# ECG.net
KiCad netlist of a schematic drawn in EAGLE
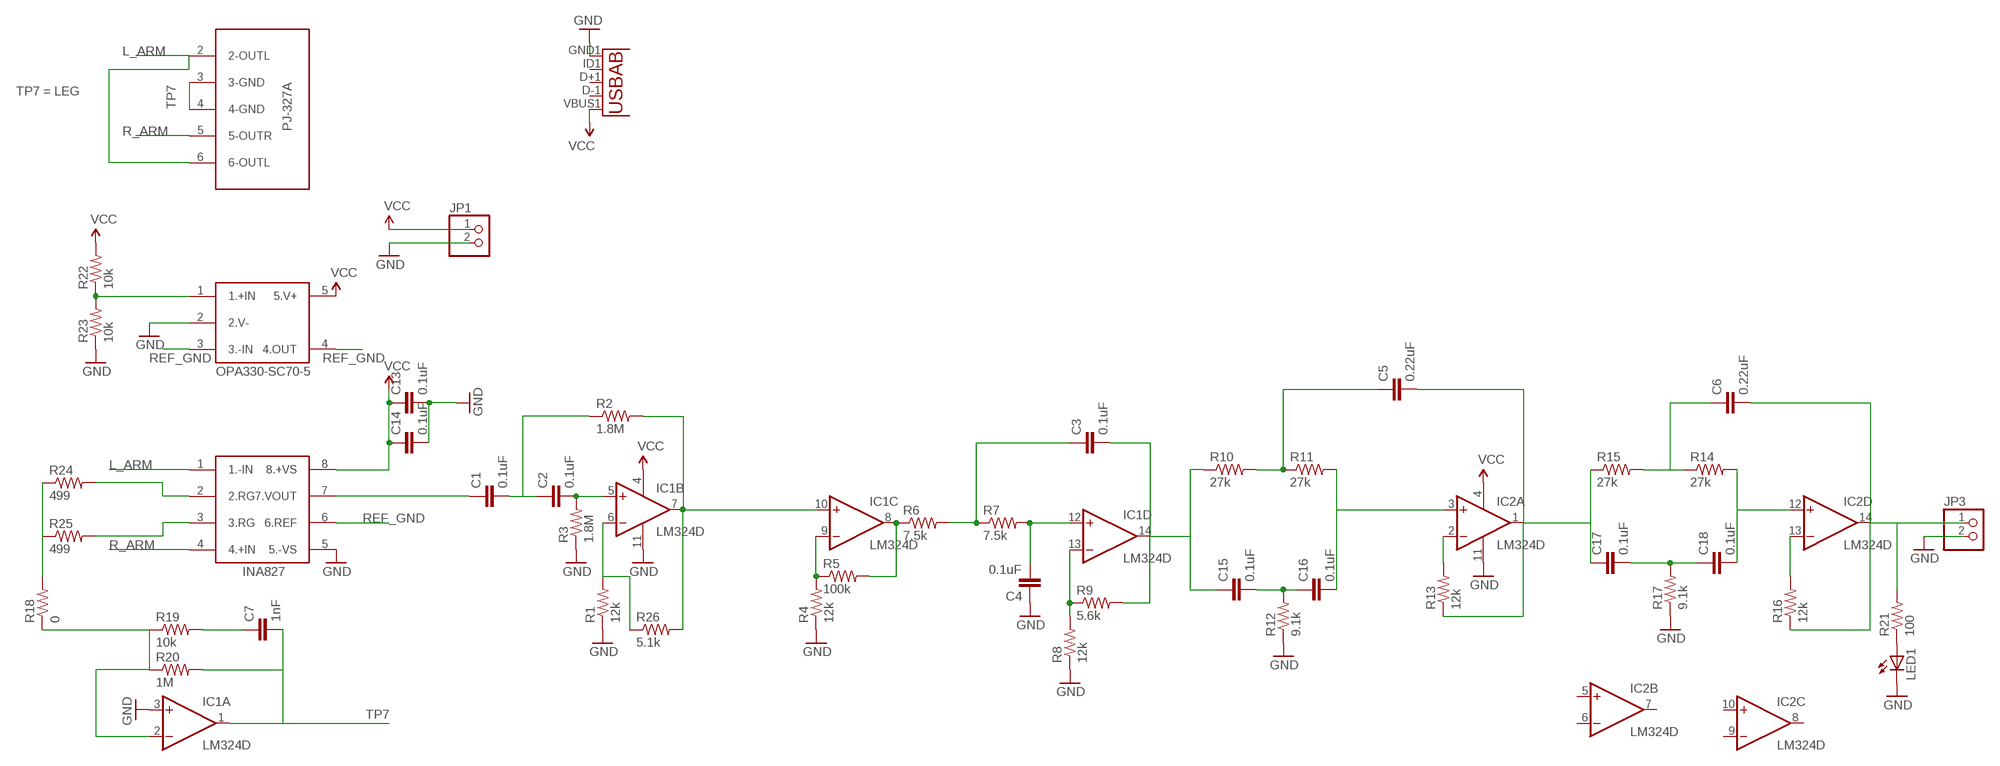
[diagram p0: schematic, sheet 1]

(export (version "E")
  (design (tool "Eeschema 10.0.6"))
  (components
    (comp (ref "C1")
      (value "0.1uF")
      (footprint "eagle-import:0603-CAP")
      (libsource (lib "eagle-import") (part "0.22UF-25V-10%(0603)"))
    )
    (comp (ref "C2")
      (value "0.1uF")
      (footprint "eagle-import:0603-CAP")
      (libsource (lib "eagle-import") (part "0.22UF-25V-10%(0603)"))
    )
    (comp (ref "C3")
      (value "0.1uF")
      (footprint "eagle-import:0603-CAP")
      (libsource (lib "eagle-import") (part "0.22UF-25V-10%(0603)"))
    )
    (comp (ref "C4")
      (value "0.1uF")
      (footprint "eagle-import:0603-CAP")
      (libsource (lib "eagle-import") (part "0.22UF-25V-10%(0603)"))
    )
    (comp (ref "C5")
      (value "0.22uF")
      (footprint "eagle-import:0603-CAP")
      (libsource (lib "eagle-import") (part "0.22UF-25V-10%(0603)"))
    )
    (comp (ref "C6")
      (value "0.22uF")
      (footprint "eagle-import:0603-CAP")
      (libsource (lib "eagle-import") (part "0.22UF-25V-10%(0603)"))
    )
    (comp (ref "C7")
      (value "1nF")
      (footprint "eagle-import:0603-CAP")
      (libsource (lib "eagle-import") (part "0.22UF-25V-10%(0603)"))
    )
    (comp (ref "C13")
      (value "0.1uF")
      (footprint "eagle-import:0603-CAP")
      (libsource (lib "eagle-import") (part "0.22UF-25V-10%(0603)"))
    )
    (comp (ref "C14")
      (value "0.1uF")
      (footprint "eagle-import:0603-CAP")
      (libsource (lib "eagle-import") (part "0.22UF-25V-10%(0603)"))
    )
    (comp (ref "C15")
      (value "0.1uF")
      (footprint "eagle-import:0603-CAP")
      (libsource (lib "eagle-import") (part "0.22UF-25V-10%(0603)"))
    )
    (comp (ref "C16")
      (value "0.1uF")
      (footprint "eagle-import:0603-CAP")
      (libsource (lib "eagle-import") (part "0.22UF-25V-10%(0603)"))
    )
    (comp (ref "C17")
      (value "0.1uF")
      (footprint "eagle-import:0603-CAP")
      (libsource (lib "eagle-import") (part "0.22UF-25V-10%(0603)"))
    )
    (comp (ref "C18")
      (value "0.1uF")
      (footprint "eagle-import:0603-CAP")
      (libsource (lib "eagle-import") (part "0.22UF-25V-10%(0603)"))
    )
    (comp (ref "IC1")
      (value "LM324D")
      (footprint "eagle-import:SO14")
      (libsource (lib "eagle-import") (part "LM324D"))
    )
    (comp (ref "IC2")
      (value "LM324D")
      (footprint "eagle-import:SO14")
      (libsource (lib "eagle-import") (part "LM324D"))
    )
    (comp (ref "JP1")
      (value "PINHD-1X2")
      (footprint "eagle-import:1X02")
      (libsource (lib "eagle-import") (part "PINHD-1X2"))
    )
    (comp (ref "JP3")
      (value "PINHD-1X2")
      (footprint "eagle-import:1X02")
      (libsource (lib "eagle-import") (part "PINHD-1X2"))
    )
    (comp (ref "LED1")
      (value "LEDCHIPLED_0603")
      (footprint "eagle-import:CHIPLED_0603")
      (libsource (lib "eagle-import") (part "LEDCHIPLED_0603"))
    )
    (comp (ref "R1")
      (value "12k")
      (footprint "eagle-import:0603-RES")
      (libsource (lib "eagle-import") (part "1.2MOHMS-1/10W-1%(0603)"))
    )
    (comp (ref "R2")
      (value "1.8M")
      (footprint "eagle-import:0603-RES")
      (libsource (lib "eagle-import") (part "1.2MOHMS-1/10W-1%(0603)"))
    )
    (comp (ref "R3")
      (value "1.8M")
      (footprint "eagle-import:0603-RES")
      (libsource (lib "eagle-import") (part "1.2MOHMS-1/10W-1%(0603)"))
    )
    (comp (ref "R4")
      (value "12k")
      (footprint "eagle-import:0603-RES")
      (libsource (lib "eagle-import") (part "1.2MOHMS-1/10W-1%(0603)"))
    )
    (comp (ref "R5")
      (value "100k")
      (footprint "eagle-import:0603-RES")
      (libsource (lib "eagle-import") (part "1.2MOHMS-1/10W-1%(0603)"))
    )
    (comp (ref "R6")
      (value "7.5k")
      (footprint "eagle-import:0603-RES")
      (libsource (lib "eagle-import") (part "1.2MOHMS-1/10W-1%(0603)"))
    )
    (comp (ref "R7")
      (value "7.5k")
      (footprint "eagle-import:0603-RES")
      (libsource (lib "eagle-import") (part "1.2MOHMS-1/10W-1%(0603)"))
    )
    (comp (ref "R8")
      (value "12k")
      (footprint "eagle-import:0603-RES")
      (libsource (lib "eagle-import") (part "1.2MOHMS-1/10W-1%(0603)"))
    )
    (comp (ref "R9")
      (value "5.6k")
      (footprint "eagle-import:0603-RES")
      (libsource (lib "eagle-import") (part "1.2MOHMS-1/10W-1%(0603)"))
    )
    (comp (ref "R10")
      (value "27k")
      (footprint "eagle-import:0603-RES")
      (libsource (lib "eagle-import") (part "1.2MOHMS-1/10W-1%(0603)"))
    )
    (comp (ref "R11")
      (value "27k")
      (footprint "eagle-import:0603-RES")
      (libsource (lib "eagle-import") (part "1.2MOHMS-1/10W-1%(0603)"))
    )
    (comp (ref "R12")
      (value "9.1k")
      (footprint "eagle-import:0603-RES")
      (libsource (lib "eagle-import") (part "1.2MOHMS-1/10W-1%(0603)"))
    )
    (comp (ref "R13")
      (value "12k")
      (footprint "eagle-import:0603-RES")
      (libsource (lib "eagle-import") (part "1.2MOHMS-1/10W-1%(0603)"))
    )
    (comp (ref "R14")
      (value "27k")
      (footprint "eagle-import:0603-RES")
      (libsource (lib "eagle-import") (part "1.2MOHMS-1/10W-1%(0603)"))
    )
    (comp (ref "R15")
      (value "27k")
      (footprint "eagle-import:0603-RES")
      (libsource (lib "eagle-import") (part "1.2MOHMS-1/10W-1%(0603)"))
    )
    (comp (ref "R16")
      (value "12k")
      (footprint "eagle-import:0603-RES")
      (libsource (lib "eagle-import") (part "1.2MOHMS-1/10W-1%(0603)"))
    )
    (comp (ref "R17")
      (value "9.1k")
      (footprint "eagle-import:0603-RES")
      (libsource (lib "eagle-import") (part "1.2MOHMS-1/10W-1%(0603)"))
    )
    (comp (ref "R18")
      (value "0")
      (footprint "eagle-import:0603-RES")
      (libsource (lib "eagle-import") (part "1.2MOHMS-1/10W-1%(0603)"))
    )
    (comp (ref "R19")
      (value "10k")
      (footprint "eagle-import:0603-RES")
      (libsource (lib "eagle-import") (part "1.2MOHMS-1/10W-1%(0603)"))
    )
    (comp (ref "R20")
      (value "1M")
      (footprint "eagle-import:0603-RES")
      (libsource (lib "eagle-import") (part "1.2MOHMS-1/10W-1%(0603)"))
    )
    (comp (ref "R21")
      (value "100")
      (footprint "eagle-import:0603-RES")
      (libsource (lib "eagle-import") (part "1.2MOHMS-1/10W-1%(0603)"))
    )
    (comp (ref "R22")
      (value "10k")
      (footprint "eagle-import:0603-RES")
      (libsource (lib "eagle-import") (part "1.2MOHMS-1/10W-1%(0603)"))
    )
    (comp (ref "R23")
      (value "10k")
      (footprint "eagle-import:0603-RES")
      (libsource (lib "eagle-import") (part "1.2MOHMS-1/10W-1%(0603)"))
    )
    (comp (ref "R24")
      (value "499")
      (footprint "eagle-import:0603-RES")
      (libsource (lib "eagle-import") (part "1.2MOHMS-1/10W-1%(0603)"))
    )
    (comp (ref "R25")
      (value "499")
      (footprint "eagle-import:0603-RES")
      (libsource (lib "eagle-import") (part "1.2MOHMS-1/10W-1%(0603)"))
    )
    (comp (ref "R26")
      (value "5.1k")
      (footprint "eagle-import:0603-RES")
      (libsource (lib "eagle-import") (part "1.2MOHMS-1/10W-1%(0603)"))
    )
    (comp (ref "U$1")
      (value "OPA330-SC70-5")
      (footprint "eagle-import:OPA330-SC70-5")
      (libsource (lib "eagle-import") (part "OPA330-SC70-5"))
    )
    (comp (ref "U$2")
      (value "INA827")
      (footprint "eagle-import:INA827")
      (libsource (lib "eagle-import") (part "INA827"))
    )
    (comp (ref "U$3")
      (value "PJ-327A")
      (footprint "eagle-import:PJ-327A")
      (libsource (lib "eagle-import") (part "PJ-327A"))
    )
    (comp (ref "U1")
      (value "USB\"\"")
      (footprint "eagle-import:USB-MICRO-SMD")
      (libsource (lib "eagle-import") (part "USB{dblquote}{dblquote}"))
    )
  )
  (nets
    (net (code "1") (name "/L_ARM") (class "Default")
      (node (ref "U$2") (pin "1") (pinfunction "1.-IN_1") (pintype "bidirectional"))
      (node (ref "U$3") (pin "2") (pinfunction "2-OUTL_2") (pintype "bidirectional"))
      (node (ref "U$3") (pin "6") (pinfunction "6-OUTL_6") (pintype "bidirectional"))
    )
    (net (code "2") (name "/REF_GND") (class "Default")
      (node (ref "U$1") (pin "3") (pinfunction "3.-IN_3") (pintype "bidirectional"))
      (node (ref "U$1") (pin "4") (pinfunction "4.OUT_4") (pintype "bidirectional"))
      (node (ref "U$2") (pin "6") (pinfunction "6.REF_6") (pintype "bidirectional"))
    )
    (net (code "3") (name "/R_ARM") (class "Default")
      (node (ref "U$2") (pin "4") (pinfunction "4.+IN_4") (pintype "bidirectional"))
      (node (ref "U$3") (pin "5") (pinfunction "5-OUTR_5") (pintype "bidirectional"))
    )
    (net (code "4") (name "/TP7") (class "Default")
      (node (ref "C7") (pin "2") (pinfunction "2_2") (pintype "passive"))
      (node (ref "IC1") (pin "1") (pinfunction "OUT_1") (pintype "output"))
      (node (ref "R20") (pin "2") (pinfunction "2_2") (pintype "passive"))
      (node (ref "U$3") (pin "3") (pinfunction "3-GND_3") (pintype "bidirectional"))
      (node (ref "U$3") (pin "4") (pinfunction "4-GND_4") (pintype "bidirectional"))
    )
    (net (code "5") (name "GND") (class "Default")
      (node (ref "C13") (pin "2") (pinfunction "2_2") (pintype "passive"))
      (node (ref "C14") (pin "2") (pinfunction "2_2") (pintype "passive"))
      (node (ref "C4") (pin "1") (pinfunction "1_1") (pintype "passive"))
      (node (ref "IC1") (pin "11") (pinfunction "V-_11") (pintype "power_in"))
      (node (ref "IC1") (pin "3") (pinfunction "+IN_3") (pintype "input"))
      (node (ref "IC2") (pin "11") (pinfunction "V-_11") (pintype "power_in"))
      (node (ref "JP1") (pin "2") (pinfunction "2_2") (pintype "passive"))
      (node (ref "JP3") (pin "2") (pinfunction "2_2") (pintype "passive"))
      (node (ref "LED1") (pin "C") (pinfunction "C_C") (pintype "passive"))
      (node (ref "R1") (pin "1") (pinfunction "1_1") (pintype "passive"))
      (node (ref "R12") (pin "1") (pinfunction "1_1") (pintype "passive"))
      (node (ref "R17") (pin "1") (pinfunction "1_1") (pintype "passive"))
      (node (ref "R23") (pin "1") (pinfunction "1_1") (pintype "passive"))
      (node (ref "R3") (pin "1") (pinfunction "1_1") (pintype "passive"))
      (node (ref "R4") (pin "1") (pinfunction "1_1") (pintype "passive"))
      (node (ref "R8") (pin "1") (pinfunction "1_1") (pintype "passive"))
      (node (ref "U$1") (pin "2") (pinfunction "2.V-_2") (pintype "bidirectional"))
      (node (ref "U$2") (pin "5") (pinfunction "5.-VS_5") (pintype "bidirectional"))
      (node (ref "U1") (pin "GND1") (pinfunction "GND_GND1") (pintype "bidirectional"))
    )
    (net (code "6") (name "Net-(C1-Pad2)") (class "Default")
      (node (ref "C1") (pin "2") (pinfunction "2_2") (pintype "passive"))
      (node (ref "C2") (pin "1") (pinfunction "1_1") (pintype "passive"))
      (node (ref "R2") (pin "1") (pinfunction "1_1") (pintype "passive"))
    )
    (net (code "7") (name "Net-(C3-Pad1)") (class "Default")
      (node (ref "C3") (pin "1") (pinfunction "1_1") (pintype "passive"))
      (node (ref "R6") (pin "2") (pinfunction "2_2") (pintype "passive"))
      (node (ref "R7") (pin "1") (pinfunction "1_1") (pintype "passive"))
    )
    (net (code "8") (name "Net-(C5-Pad1)") (class "Default")
      (node (ref "C5") (pin "1") (pinfunction "1_1") (pintype "passive"))
      (node (ref "R10") (pin "2") (pinfunction "2_2") (pintype "passive"))
      (node (ref "R11") (pin "1") (pinfunction "1_1") (pintype "passive"))
    )
    (net (code "9") (name "Net-(C6-Pad1)") (class "Default")
      (node (ref "C6") (pin "1") (pinfunction "1_1") (pintype "passive"))
      (node (ref "R14") (pin "1") (pinfunction "1_1") (pintype "passive"))
      (node (ref "R15") (pin "2") (pinfunction "2_2") (pintype "passive"))
    )
    (net (code "10") (name "Net-(C7-Pad1)") (class "Default")
      (node (ref "C7") (pin "1") (pinfunction "1_1") (pintype "passive"))
      (node (ref "R19") (pin "2") (pinfunction "2_2") (pintype "passive"))
    )
    (net (code "11") (name "Net-(C15-Pad2)") (class "Default")
      (node (ref "C15") (pin "2") (pinfunction "2_2") (pintype "passive"))
      (node (ref "C16") (pin "1") (pinfunction "1_1") (pintype "passive"))
      (node (ref "R12") (pin "2") (pinfunction "2_2") (pintype "passive"))
    )
    (net (code "12") (name "Net-(C17-Pad2)") (class "Default")
      (node (ref "C17") (pin "2") (pinfunction "2_2") (pintype "passive"))
      (node (ref "C18") (pin "1") (pinfunction "1_1") (pintype "passive"))
      (node (ref "R17") (pin "2") (pinfunction "2_2") (pintype "passive"))
    )
    (net (code "13") (name "Net-(IC1A--IN)") (class "Default")
      (node (ref "IC1") (pin "2") (pinfunction "-IN_2") (pintype "input"))
      (node (ref "R18") (pin "1") (pinfunction "1_1") (pintype "passive"))
      (node (ref "R19") (pin "1") (pinfunction "1_1") (pintype "passive"))
      (node (ref "R20") (pin "1") (pinfunction "1_1") (pintype "passive"))
    )
    (net (code "14") (name "Net-(IC1B-+IN)") (class "Default")
      (node (ref "C2") (pin "2") (pinfunction "2_2") (pintype "passive"))
      (node (ref "IC1") (pin "5") (pinfunction "+IN_5") (pintype "input"))
      (node (ref "R3") (pin "2") (pinfunction "2_2") (pintype "passive"))
    )
    (net (code "15") (name "Net-(IC1B--IN)") (class "Default")
      (node (ref "IC1") (pin "6") (pinfunction "-IN_6") (pintype "input"))
      (node (ref "R1") (pin "2") (pinfunction "2_2") (pintype "passive"))
      (node (ref "R26") (pin "1") (pinfunction "1_1") (pintype "passive"))
    )
    (net (code "16") (name "Net-(IC1B-OUT)") (class "Default")
      (node (ref "IC1") (pin "10") (pinfunction "+IN_10") (pintype "input"))
      (node (ref "IC1") (pin "7") (pinfunction "OUT_7") (pintype "output"))
      (node (ref "R2") (pin "2") (pinfunction "2_2") (pintype "passive"))
      (node (ref "R26") (pin "2") (pinfunction "2_2") (pintype "passive"))
    )
    (net (code "17") (name "Net-(IC1C--IN)") (class "Default")
      (node (ref "IC1") (pin "9") (pinfunction "-IN_9") (pintype "input"))
      (node (ref "R4") (pin "2") (pinfunction "2_2") (pintype "passive"))
      (node (ref "R5") (pin "1") (pinfunction "1_1") (pintype "passive"))
    )
    (net (code "18") (name "Net-(IC1C-OUT)") (class "Default")
      (node (ref "IC1") (pin "8") (pinfunction "OUT_8") (pintype "output"))
      (node (ref "R5") (pin "2") (pinfunction "2_2") (pintype "passive"))
      (node (ref "R6") (pin "1") (pinfunction "1_1") (pintype "passive"))
    )
    (net (code "19") (name "Net-(IC1D-+IN)") (class "Default")
      (node (ref "C4") (pin "2") (pinfunction "2_2") (pintype "passive"))
      (node (ref "IC1") (pin "12") (pinfunction "+IN_12") (pintype "input"))
      (node (ref "R7") (pin "2") (pinfunction "2_2") (pintype "passive"))
    )
    (net (code "20") (name "Net-(IC1D--IN)") (class "Default")
      (node (ref "IC1") (pin "13") (pinfunction "-IN_13") (pintype "input"))
      (node (ref "R8") (pin "2") (pinfunction "2_2") (pintype "passive"))
      (node (ref "R9") (pin "1") (pinfunction "1_1") (pintype "passive"))
    )
    (net (code "21") (name "Net-(IC1D-OUT)") (class "Default")
      (node (ref "C15") (pin "1") (pinfunction "1_1") (pintype "passive"))
      (node (ref "C3") (pin "2") (pinfunction "2_2") (pintype "passive"))
      (node (ref "IC1") (pin "14") (pinfunction "OUT_14") (pintype "output"))
      (node (ref "R10") (pin "1") (pinfunction "1_1") (pintype "passive"))
      (node (ref "R9") (pin "2") (pinfunction "2_2") (pintype "passive"))
    )
    (net (code "22") (name "Net-(IC2A-+IN)") (class "Default")
      (node (ref "C16") (pin "2") (pinfunction "2_2") (pintype "passive"))
      (node (ref "IC2") (pin "3") (pinfunction "+IN_3") (pintype "input"))
      (node (ref "R11") (pin "2") (pinfunction "2_2") (pintype "passive"))
    )
    (net (code "23") (name "Net-(IC2A--IN)") (class "Default")
      (node (ref "IC2") (pin "2") (pinfunction "-IN_2") (pintype "input"))
      (node (ref "R13") (pin "2") (pinfunction "2_2") (pintype "passive"))
    )
    (net (code "24") (name "Net-(IC2A-OUT)") (class "Default")
      (node (ref "C17") (pin "1") (pinfunction "1_1") (pintype "passive"))
      (node (ref "C5") (pin "2") (pinfunction "2_2") (pintype "passive"))
      (node (ref "IC2") (pin "1") (pinfunction "OUT_1") (pintype "output"))
      (node (ref "R13") (pin "1") (pinfunction "1_1") (pintype "passive"))
      (node (ref "R15") (pin "1") (pinfunction "1_1") (pintype "passive"))
    )
    (net (code "25") (name "Net-(IC2D-+IN)") (class "Default")
      (node (ref "C18") (pin "2") (pinfunction "2_2") (pintype "passive"))
      (node (ref "IC2") (pin "12") (pinfunction "+IN_12") (pintype "input"))
      (node (ref "R14") (pin "2") (pinfunction "2_2") (pintype "passive"))
    )
    (net (code "26") (name "Net-(IC2D--IN)") (class "Default")
      (node (ref "IC2") (pin "13") (pinfunction "-IN_13") (pintype "input"))
      (node (ref "R16") (pin "2") (pinfunction "2_2") (pintype "passive"))
    )
    (net (code "27") (name "Net-(IC2D-OUT)") (class "Default")
      (node (ref "C6") (pin "2") (pinfunction "2_2") (pintype "passive"))
      (node (ref "IC2") (pin "14") (pinfunction "OUT_14") (pintype "output"))
      (node (ref "JP3") (pin "1") (pinfunction "1_1") (pintype "passive"))
      (node (ref "R16") (pin "1") (pinfunction "1_1") (pintype "passive"))
      (node (ref "R21") (pin "2") (pinfunction "2_2") (pintype "passive"))
    )
    (net (code "28") (name "Net-(LED1-PadA)") (class "Default")
      (node (ref "LED1") (pin "A") (pinfunction "A_A") (pintype "passive"))
      (node (ref "R21") (pin "1") (pinfunction "1_1") (pintype "passive"))
    )
    (net (code "29") (name "Net-(R18-Pad2)") (class "Default")
      (node (ref "R18") (pin "2") (pinfunction "2_2") (pintype "passive"))
      (node (ref "R24") (pin "1") (pinfunction "1_1") (pintype "passive"))
      (node (ref "R25") (pin "1") (pinfunction "1_1") (pintype "passive"))
    )
    (net (code "30") (name "Net-(U$1-1.+IN)") (class "Default")
      (node (ref "R22") (pin "1") (pinfunction "1_1") (pintype "passive"))
      (node (ref "R23") (pin "2") (pinfunction "2_2") (pintype "passive"))
      (node (ref "U$1") (pin "1") (pinfunction "1.+IN_1") (pintype "bidirectional"))
    )
    (net (code "31") (name "Net-(U$2-2.RG)") (class "Default")
      (node (ref "R24") (pin "2") (pinfunction "2_2") (pintype "passive"))
      (node (ref "U$2") (pin "2") (pinfunction "2.RG_2") (pintype "bidirectional"))
    )
    (net (code "32") (name "Net-(U$2-3.RG)") (class "Default")
      (node (ref "R25") (pin "2") (pinfunction "2_2") (pintype "passive"))
      (node (ref "U$2") (pin "3") (pinfunction "3.RG_3") (pintype "bidirectional"))
    )
    (net (code "33") (name "Net-(U$2-7.VOUT)") (class "Default")
      (node (ref "C1") (pin "1") (pinfunction "1_1") (pintype "passive"))
      (node (ref "U$2") (pin "7") (pinfunction "7.VOUT_7") (pintype "bidirectional"))
    )
    (net (code "34") (name "VCC") (class "Default")
      (node (ref "C13") (pin "1") (pinfunction "1_1") (pintype "passive"))
      (node (ref "C14") (pin "1") (pinfunction "1_1") (pintype "passive"))
      (node (ref "IC1") (pin "4") (pinfunction "V+_4") (pintype "power_in"))
      (node (ref "IC2") (pin "4") (pinfunction "V+_4") (pintype "power_in"))
      (node (ref "JP1") (pin "1") (pinfunction "1_1") (pintype "passive"))
      (node (ref "R22") (pin "2") (pinfunction "2_2") (pintype "passive"))
      (node (ref "U$1") (pin "5") (pinfunction "5.V+_5") (pintype "bidirectional"))
      (node (ref "U$2") (pin "8") (pinfunction "8.+VS_8") (pintype "bidirectional"))
      (node (ref "U1") (pin "VBUS1") (pinfunction "VBUS_VBUS1") (pintype "bidirectional"))
    )
    (net (code "35") (name "unconnected-(IC2B-+IN-Pad5)") (class "Default")
      (node (ref "IC2") (pin "5") (pinfunction "+IN_5") (pintype "input"))
    )
    (net (code "36") (name "unconnected-(IC2B--IN-Pad6)") (class "Default")
      (node (ref "IC2") (pin "6") (pinfunction "-IN_6") (pintype "input"))
    )
    (net (code "37") (name "unconnected-(IC2B-OUT-Pad7)") (class "Default")
      (node (ref "IC2") (pin "7") (pinfunction "OUT_7") (pintype "output"))
    )
    (net (code "38") (name "unconnected-(IC2C-+IN-Pad10)") (class "Default")
      (node (ref "IC2") (pin "10") (pinfunction "+IN_10") (pintype "input"))
    )
    (net (code "39") (name "unconnected-(IC2C--IN-Pad9)") (class "Default")
      (node (ref "IC2") (pin "9") (pinfunction "-IN_9") (pintype "input"))
    )
    (net (code "40") (name "unconnected-(IC2C-OUT-Pad8)") (class "Default")
      (node (ref "IC2") (pin "8") (pinfunction "OUT_8") (pintype "output"))
    )
    (net (code "41") (name "unconnected-(U1-D+-PadD+1)") (class "Default")
      (node (ref "U1") (pin "D+1") (pinfunction "D+_D+1") (pintype "bidirectional"))
    )
    (net (code "42") (name "unconnected-(U1-D--PadD-1)") (class "Default")
      (node (ref "U1") (pin "D-1") (pinfunction "D-_D-1") (pintype "bidirectional"))
    )
    (net (code "43") (name "unconnected-(U1-USBID-PadID1)") (class "Default")
      (node (ref "U1") (pin "ID1") (pinfunction "USBID_ID1") (pintype "bidirectional"))
    )
  )
)
